# l6727a-5v.net
KiCad netlist of a schematic drawn in EAGLE
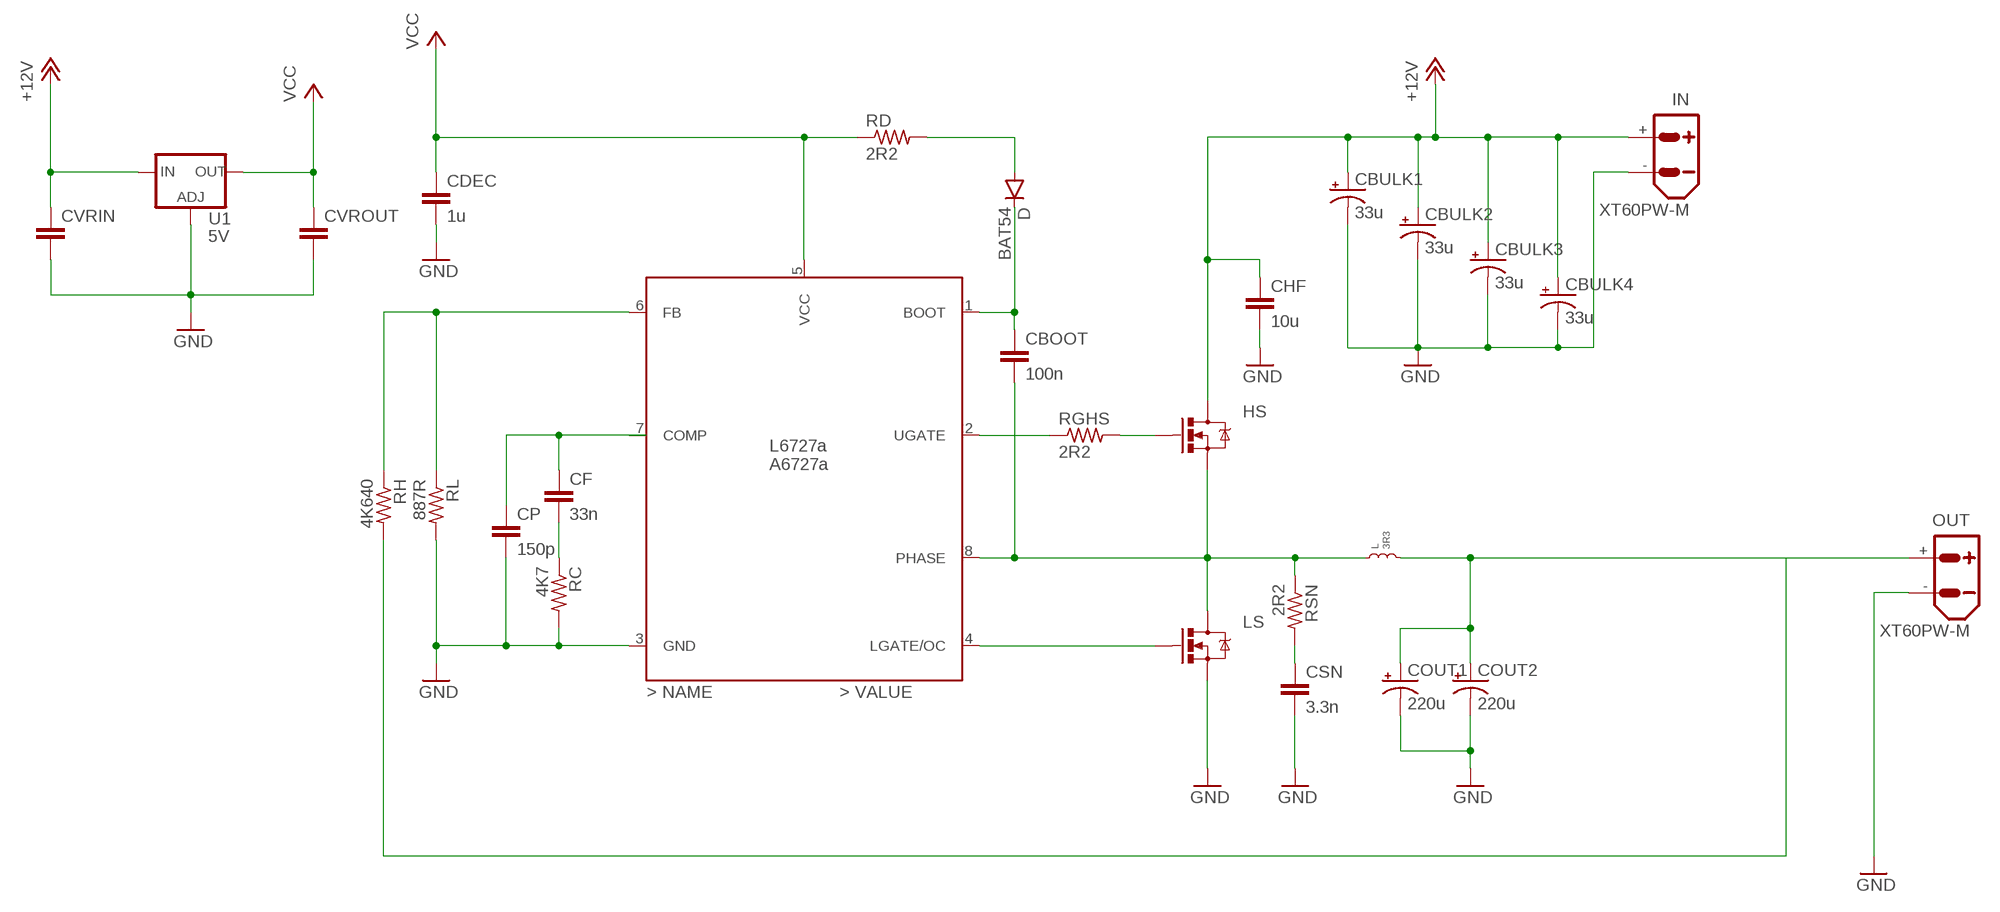
[diagram p0: schematic, sheet 1]

(export (version "E")
  (design (tool "Eeschema 10.0.6"))
  (components
    (comp (ref "CBOOT")
      (value "100n")
      (footprint "eagle-import:C0603")
      (libsource (lib "eagle-import") (part "C-EUC0603"))
    )
    (comp (ref "CBULK1")
      (value "33u")
      (footprint "eagle-import:SANYO-OSCON_SMD_E7")
      (libsource (lib "eagle-import") (part "CPOL-USSANYO_SMD_E7"))
    )
    (comp (ref "CBULK2")
      (value "33u")
      (footprint "eagle-import:SANYO-OSCON_SMD_E7")
      (libsource (lib "eagle-import") (part "CPOL-USSANYO_SMD_E7"))
    )
    (comp (ref "CBULK3")
      (value "33u")
      (footprint "eagle-import:SANYO-OSCON_SMD_E7")
      (libsource (lib "eagle-import") (part "CPOL-USSANYO_SMD_E7"))
    )
    (comp (ref "CBULK4")
      (value "33u")
      (footprint "eagle-import:SANYO-OSCON_SMD_E7")
      (libsource (lib "eagle-import") (part "CPOL-USSANYO_SMD_E7"))
    )
    (comp (ref "CDEC")
      (value "1u")
      (footprint "eagle-import:C0603")
      (libsource (lib "eagle-import") (part "C-EUC0603"))
    )
    (comp (ref "CF")
      (value "33n")
      (footprint "eagle-import:C0603")
      (libsource (lib "eagle-import") (part "C-EUC0603"))
    )
    (comp (ref "CHF")
      (value "10u")
      (footprint "eagle-import:C1206")
      (libsource (lib "eagle-import") (part "C-EUC1206"))
    )
    (comp (ref "COUT1")
      (value "220u")
      (footprint "eagle-import:SANYO-OSCON_SMD_E7")
      (libsource (lib "eagle-import") (part "CPOL-USSANYO_SMD_E7"))
    )
    (comp (ref "COUT2")
      (value "220u")
      (footprint "eagle-import:SANYO-OSCON_SMD_E7")
      (libsource (lib "eagle-import") (part "CPOL-USSANYO_SMD_E7"))
    )
    (comp (ref "CP")
      (value "150p")
      (footprint "eagle-import:C0603")
      (libsource (lib "eagle-import") (part "C-EUC0603"))
    )
    (comp (ref "CSN")
      (value "3.3n")
      (footprint "eagle-import:C0603")
      (libsource (lib "eagle-import") (part "C-EUC0603"))
    )
    (comp (ref "CVRIN")
      (value "C-EUC1206")
      (footprint "eagle-import:C1206")
      (libsource (lib "eagle-import") (part "C-EUC1206"))
    )
    (comp (ref "CVROUT")
      (value "C-EUC1206")
      (footprint "eagle-import:C1206")
      (libsource (lib "eagle-import") (part "C-EUC1206"))
    )
    (comp (ref "D")
      (value "BAT54")
      (footprint "eagle-import:SOD-123")
      (libsource (lib "eagle-import") (part "DIODESOD123"))
    )
    (comp (ref "HS")
      (value "MOSFET-NCHANNELFDS6630A")
      (footprint "eagle-import:SO08")
      (libsource (lib "eagle-import") (part "MOSFET-NCHANNELFDS6630A"))
    )
    (comp (ref "IC1")
      (value "L6727A")
      (footprint "eagle-import:SO-08")
      (libsource (lib "eagle-import") (part "L6727A"))
    )
    (comp (ref "IN")
      (value "XT60PW-M")
      (footprint "eagle-import:XT60PW-M")
      (libsource (lib "eagle-import") (part "XT60PW-M"))
    )
    (comp (ref "L")
      (value "3R3")
      (footprint "eagle-import:XAL1010")
      (libsource (lib "eagle-import") (part "INDUCTOR.XAL1010"))
    )
    (comp (ref "LS")
      (value "MOSFET-NCHANNELFDS6630A")
      (footprint "eagle-import:SO08")
      (libsource (lib "eagle-import") (part "MOSFET-NCHANNELFDS6630A"))
    )
    (comp (ref "OUT")
      (value "XT60PW-M")
      (footprint "eagle-import:XT60PW-M")
      (libsource (lib "eagle-import") (part "XT60PW-M"))
    )
    (comp (ref "RC")
      (value "4K7")
      (footprint "eagle-import:R0603")
      (libsource (lib "eagle-import") (part "R-US_R0603"))
    )
    (comp (ref "RD")
      (value "2R2")
      (footprint "eagle-import:R0603")
      (libsource (lib "eagle-import") (part "R-US_R0603"))
    )
    (comp (ref "RGHS")
      (value "2R2")
      (footprint "eagle-import:R0603")
      (libsource (lib "eagle-import") (part "R-US_R0603"))
    )
    (comp (ref "RH")
      (value "4K640")
      (footprint "eagle-import:R0603")
      (libsource (lib "eagle-import") (part "R-US_R0603"))
    )
    (comp (ref "RL")
      (value "887R")
      (footprint "eagle-import:R0603")
      (libsource (lib "eagle-import") (part "R-US_R0603"))
    )
    (comp (ref "RSN")
      (value "2R2")
      (footprint "eagle-import:R0603")
      (libsource (lib "eagle-import") (part "R-US_R0603"))
    )
    (comp (ref "U1")
      (value "5V")
      (footprint "eagle-import:SOT223")
      (libsource (lib "eagle-import") (part "V_REG_317SMD"))
    )
  )
  (nets
    (net (code "1") (name "+12V") (class "Default")
      (node (ref "CBULK1") (pin "+") (pinfunction "+_+") (pintype "passive"))
      (node (ref "CBULK2") (pin "+") (pinfunction "+_+") (pintype "passive"))
      (node (ref "CBULK3") (pin "+") (pinfunction "+_+") (pintype "passive"))
      (node (ref "CBULK4") (pin "+") (pinfunction "+_+") (pintype "passive"))
      (node (ref "CHF") (pin "1") (pinfunction "1_1") (pintype "passive"))
      (node (ref "CVRIN") (pin "1") (pinfunction "1_1") (pintype "passive"))
      (node (ref "HS") (pin "5") (pinfunction "D_5") (pintype "passive"))
      (node (ref "HS") (pin "6") (pinfunction "D_6") (pintype "passive"))
      (node (ref "HS") (pin "7") (pinfunction "D_7") (pintype "passive"))
      (node (ref "HS") (pin "8") (pinfunction "D_8") (pintype "passive"))
      (node (ref "IN") (pin "+") (pinfunction "+_+") (pintype "power_in"))
      (node (ref "U1") (pin "3") (pinfunction "IN_3") (pintype "input"))
    )
    (net (code "2") (name "GND") (class "Default")
      (node (ref "CBULK1") (pin "-") (pinfunction "-_-") (pintype "passive"))
      (node (ref "CBULK2") (pin "-") (pinfunction "-_-") (pintype "passive"))
      (node (ref "CBULK3") (pin "-") (pinfunction "-_-") (pintype "passive"))
      (node (ref "CBULK4") (pin "-") (pinfunction "-_-") (pintype "passive"))
      (node (ref "CDEC") (pin "2") (pinfunction "2_2") (pintype "passive"))
      (node (ref "CHF") (pin "2") (pinfunction "2_2") (pintype "passive"))
      (node (ref "COUT1") (pin "-") (pinfunction "-_-") (pintype "passive"))
      (node (ref "COUT2") (pin "-") (pinfunction "-_-") (pintype "passive"))
      (node (ref "CP") (pin "2") (pinfunction "2_2") (pintype "passive"))
      (node (ref "CSN") (pin "2") (pinfunction "2_2") (pintype "passive"))
      (node (ref "CVRIN") (pin "2") (pinfunction "2_2") (pintype "passive"))
      (node (ref "CVROUT") (pin "2") (pinfunction "2_2") (pintype "passive"))
      (node (ref "IC1") (pin "3") (pinfunction "GND_3") (pintype "power_in"))
      (node (ref "IN") (pin "-") (pinfunction "-_-") (pintype "power_in"))
      (node (ref "LS") (pin "1") (pinfunction "S_1") (pintype "passive"))
      (node (ref "LS") (pin "2") (pinfunction "S_2") (pintype "passive"))
      (node (ref "LS") (pin "3") (pinfunction "S_3") (pintype "passive"))
      (node (ref "OUT") (pin "-") (pinfunction "-_-") (pintype "power_in"))
      (node (ref "RC") (pin "2") (pinfunction "2_2") (pintype "passive"))
      (node (ref "RL") (pin "2") (pinfunction "2_2") (pintype "passive"))
      (node (ref "U1") (pin "1") (pinfunction "ADJ_1") (pintype "input"))
    )
    (net (code "3") (name "Net-(CF-Pad1)") (class "Default")
      (node (ref "CF") (pin "1") (pinfunction "1_1") (pintype "passive"))
      (node (ref "CP") (pin "1") (pinfunction "1_1") (pintype "passive"))
    )
    (net (code "4") (name "Net-(CF-Pad2)") (class "Default")
      (node (ref "CF") (pin "2") (pinfunction "2_2") (pintype "passive"))
      (node (ref "RC") (pin "1") (pinfunction "1_1") (pintype "passive"))
    )
    (net (code "5") (name "Net-(CSN-Pad1)") (class "Default")
      (node (ref "CSN") (pin "1") (pinfunction "1_1") (pintype "passive"))
      (node (ref "RSN") (pin "2") (pinfunction "2_2") (pintype "passive"))
    )
    (net (code "6") (name "Net-(D-PadA)") (class "Default")
      (node (ref "D") (pin "A") (pinfunction "A_A") (pintype "passive"))
      (node (ref "RD") (pin "2") (pinfunction "2_2") (pintype "passive"))
    )
    (net (code "7") (name "Net-(HS-G)") (class "Default")
      (node (ref "HS") (pin "4") (pinfunction "G_4") (pintype "passive"))
      (node (ref "RGHS") (pin "2") (pinfunction "2_2") (pintype "passive"))
    )
    (net (code "8") (name "Net-(IC1-BOOT)") (class "Default")
      (node (ref "CBOOT") (pin "1") (pinfunction "1_1") (pintype "passive"))
      (node (ref "D") (pin "C") (pinfunction "C_C") (pintype "passive"))
      (node (ref "IC1") (pin "1") (pinfunction "BOOT_1") (pintype "power_in"))
    )
    (net (code "9") (name "Net-(IC1-FB)") (class "Default")
      (node (ref "IC1") (pin "6") (pinfunction "FB_6") (pintype "input"))
      (node (ref "RH") (pin "1") (pinfunction "1_1") (pintype "passive"))
      (node (ref "RL") (pin "1") (pinfunction "1_1") (pintype "passive"))
    )
    (net (code "10") (name "Net-(IC1-LGATE{slash}OC)") (class "Default")
      (node (ref "IC1") (pin "4") (pinfunction "LGATE/OC_4") (pintype "output"))
      (node (ref "LS") (pin "4") (pinfunction "G_4") (pintype "passive"))
    )
    (net (code "11") (name "Net-(IC1-PHASE)") (class "Default")
      (node (ref "CBOOT") (pin "2") (pinfunction "2_2") (pintype "passive"))
      (node (ref "HS") (pin "1") (pinfunction "S_1") (pintype "passive"))
      (node (ref "HS") (pin "2") (pinfunction "S_2") (pintype "passive"))
      (node (ref "HS") (pin "3") (pinfunction "S_3") (pintype "passive"))
      (node (ref "IC1") (pin "8") (pinfunction "PHASE_8") (pintype "input"))
      (node (ref "L") (pin "P$1") (pinfunction "1_P$1") (pintype "passive"))
      (node (ref "LS") (pin "5") (pinfunction "D_5") (pintype "passive"))
      (node (ref "LS") (pin "6") (pinfunction "D_6") (pintype "passive"))
      (node (ref "LS") (pin "7") (pinfunction "D_7") (pintype "passive"))
      (node (ref "LS") (pin "8") (pinfunction "D_8") (pintype "passive"))
      (node (ref "RSN") (pin "1") (pinfunction "1_1") (pintype "passive"))
    )
    (net (code "12") (name "Net-(IC1-UGATE)") (class "Default")
      (node (ref "IC1") (pin "2") (pinfunction "UGATE_2") (pintype "output"))
      (node (ref "RGHS") (pin "1") (pinfunction "1_1") (pintype "passive"))
    )
    (net (code "13") (name "Net-(L-2)") (class "Default")
      (node (ref "COUT1") (pin "+") (pinfunction "+_+") (pintype "passive"))
      (node (ref "COUT2") (pin "+") (pinfunction "+_+") (pintype "passive"))
      (node (ref "L") (pin "P$2") (pinfunction "2_P$2") (pintype "passive"))
      (node (ref "OUT") (pin "+") (pinfunction "+_+") (pintype "power_in"))
      (node (ref "RH") (pin "2") (pinfunction "2_2") (pintype "passive"))
    )
    (net (code "14") (name "VCC") (class "Default")
      (node (ref "CDEC") (pin "1") (pinfunction "1_1") (pintype "passive"))
      (node (ref "CVROUT") (pin "1") (pinfunction "1_1") (pintype "passive"))
      (node (ref "IC1") (pin "5") (pinfunction "VCC_5") (pintype "power_in"))
      (node (ref "RD") (pin "1") (pinfunction "1_1") (pintype "passive"))
      (node (ref "U1") (pin "2") (pinfunction "OUT_2") (pintype "output"))
    )
    (net (code "15") (name "unconnected-(IC1-COMP-Pad7)") (class "Default")
      (node (ref "IC1") (pin "7") (pinfunction "COMP_7") (pintype "input"))
    )
  )
)
